# Power_Distribution_V2.net
KiCad netlist of a schematic drawn in EAGLE
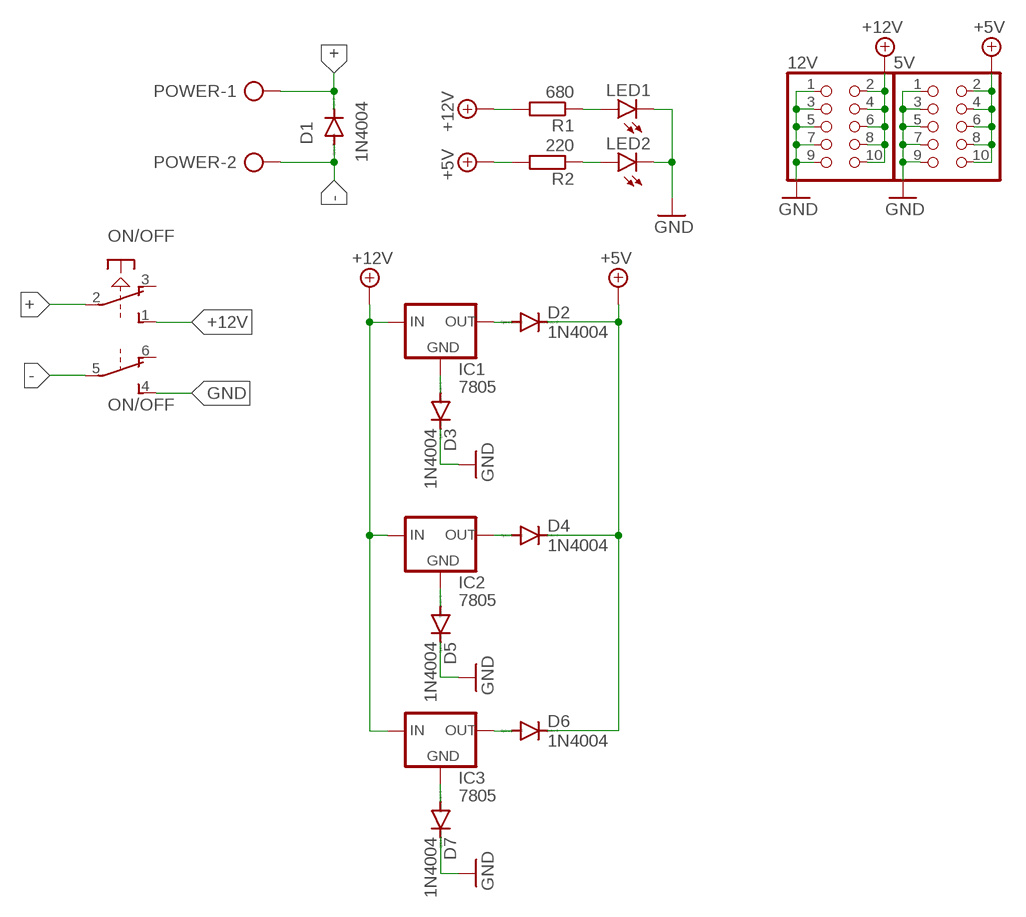
[diagram p0: schematic, sheet 1]

(export (version "E")
  (design (tool "Eeschema 10.0.6"))
  (components
    (comp (ref "5V")
      (value "PINHD-2X5")
      (footprint "eagle-import:2X05")
      (libsource (lib "eagle-import") (part "PINHD-2X5"))
    )
    (comp (ref "12V")
      (value "PINHD-2X5")
      (footprint "eagle-import:2X05")
      (libsource (lib "eagle-import") (part "PINHD-2X5"))
    )
    (comp (ref "D1")
      (value "1N4004")
      (footprint "eagle-import:DO41-10")
      (libsource (lib "eagle-import") (part "1N4004"))
    )
    (comp (ref "D2")
      (value "1N4004")
      (footprint "eagle-import:DO41-10")
      (libsource (lib "eagle-import") (part "1N4004"))
    )
    (comp (ref "D3")
      (value "1N4004")
      (footprint "eagle-import:DO41-10")
      (libsource (lib "eagle-import") (part "1N4004"))
    )
    (comp (ref "D4")
      (value "1N4004")
      (footprint "eagle-import:DO41-10")
      (libsource (lib "eagle-import") (part "1N4004"))
    )
    (comp (ref "D5")
      (value "1N4004")
      (footprint "eagle-import:DO41-10")
      (libsource (lib "eagle-import") (part "1N4004"))
    )
    (comp (ref "D6")
      (value "1N4004")
      (footprint "eagle-import:DO41-10")
      (libsource (lib "eagle-import") (part "1N4004"))
    )
    (comp (ref "D7")
      (value "1N4004")
      (footprint "eagle-import:DO41-10")
      (libsource (lib "eagle-import") (part "1N4004"))
    )
    (comp (ref "IC1")
      (value "7805")
      (footprint "eagle-import:78XXS")
      (libsource (lib "eagle-import") (part "78XXS"))
    )
    (comp (ref "IC2")
      (value "7805")
      (footprint "eagle-import:78XXS")
      (libsource (lib "eagle-import") (part "78XXS"))
    )
    (comp (ref "IC3")
      (value "7805")
      (footprint "eagle-import:78XXS")
      (libsource (lib "eagle-import") (part "78XXS"))
    )
    (comp (ref "LED1")
      (value "LED3MM")
      (footprint "eagle-import:LED3MM")
      (libsource (lib "eagle-import") (part "LED3MM"))
    )
    (comp (ref "LED2")
      (value "LED3MM")
      (footprint "eagle-import:LED3MM")
      (libsource (lib "eagle-import") (part "LED3MM"))
    )
    (comp (ref "ON/OFF")
      (value "PVA2R")
      (footprint "eagle-import:PVA2R")
      (libsource (lib "eagle-import") (part "PVA2R"))
    )
    (comp (ref "POWER")
      (value "AK500/2-H")
      (footprint "eagle-import:AK500_2-H")
      (libsource (lib "eagle-import") (part "AK500/2-H"))
    )
    (comp (ref "R1")
      (value "680")
      (footprint "eagle-import:0207_10")
      (libsource (lib "eagle-import") (part "R-EU_0207/10"))
    )
    (comp (ref "R2")
      (value "220")
      (footprint "eagle-import:0207_10")
      (libsource (lib "eagle-import") (part "R-EU_0207/10"))
    )
  )
  (nets
    (net (code "1") (name "+") (class "Default")
      (node (ref "D1") (pin "C") (pinfunction "C_C") (pintype "passive"))
      (node (ref "ON/OFF") (pin "2") (pinfunction "P_2") (pintype "passive"))
      (node (ref "POWER") (pin "1") (pinfunction "KL_1") (pintype "passive"))
    )
    (net (code "2") (name "+5V") (class "Default")
      (node (ref "5V") (pin "10") (pinfunction "10_10") (pintype "passive"))
      (node (ref "5V") (pin "2") (pinfunction "2_2") (pintype "passive"))
      (node (ref "5V") (pin "4") (pinfunction "4_4") (pintype "passive"))
      (node (ref "5V") (pin "6") (pinfunction "6_6") (pintype "passive"))
      (node (ref "5V") (pin "8") (pinfunction "8_8") (pintype "passive"))
      (node (ref "D2") (pin "C") (pinfunction "C_C") (pintype "passive"))
      (node (ref "D4") (pin "C") (pinfunction "C_C") (pintype "passive"))
      (node (ref "D6") (pin "C") (pinfunction "C_C") (pintype "passive"))
      (node (ref "R2") (pin "2") (pinfunction "2_2") (pintype "passive"))
    )
    (net (code "3") (name "+12V") (class "Default")
      (node (ref "12V") (pin "10") (pinfunction "10_10") (pintype "passive"))
      (node (ref "12V") (pin "2") (pinfunction "2_2") (pintype "passive"))
      (node (ref "12V") (pin "4") (pinfunction "4_4") (pintype "passive"))
      (node (ref "12V") (pin "6") (pinfunction "6_6") (pintype "passive"))
      (node (ref "12V") (pin "8") (pinfunction "8_8") (pintype "passive"))
      (node (ref "IC1") (pin "IN") (pinfunction "IN_IN") (pintype "input"))
      (node (ref "IC2") (pin "IN") (pinfunction "IN_IN") (pintype "input"))
      (node (ref "IC3") (pin "IN") (pinfunction "IN_IN") (pintype "input"))
      (node (ref "ON/OFF") (pin "1") (pinfunction "S_1") (pintype "passive"))
      (node (ref "R1") (pin "2") (pinfunction "2_2") (pintype "passive"))
    )
    (net (code "4") (name "-") (class "Default")
      (node (ref "D1") (pin "A") (pinfunction "A_A") (pintype "passive"))
      (node (ref "ON/OFF") (pin "5") (pinfunction "P_5") (pintype "passive"))
      (node (ref "POWER") (pin "2") (pinfunction "KL_2") (pintype "passive"))
    )
    (net (code "5") (name "GND") (class "Default")
      (node (ref "12V") (pin "1") (pinfunction "1_1") (pintype "passive"))
      (node (ref "12V") (pin "3") (pinfunction "3_3") (pintype "passive"))
      (node (ref "12V") (pin "5") (pinfunction "5_5") (pintype "passive"))
      (node (ref "12V") (pin "7") (pinfunction "7_7") (pintype "passive"))
      (node (ref "12V") (pin "9") (pinfunction "9_9") (pintype "passive"))
      (node (ref "5V") (pin "1") (pinfunction "1_1") (pintype "passive"))
      (node (ref "5V") (pin "3") (pinfunction "3_3") (pintype "passive"))
      (node (ref "5V") (pin "5") (pinfunction "5_5") (pintype "passive"))
      (node (ref "5V") (pin "7") (pinfunction "7_7") (pintype "passive"))
      (node (ref "5V") (pin "9") (pinfunction "9_9") (pintype "passive"))
      (node (ref "D3") (pin "C") (pinfunction "C_C") (pintype "passive"))
      (node (ref "D5") (pin "C") (pinfunction "C_C") (pintype "passive"))
      (node (ref "D7") (pin "C") (pinfunction "C_C") (pintype "passive"))
      (node (ref "LED1") (pin "K") (pinfunction "C_K") (pintype "passive"))
      (node (ref "LED2") (pin "K") (pinfunction "C_K") (pintype "passive"))
      (node (ref "ON/OFF") (pin "4") (pinfunction "S_4") (pintype "passive"))
    )
    (net (code "6") (name "Net-(D2-PadA)") (class "Default")
      (node (ref "D2") (pin "A") (pinfunction "A_A") (pintype "passive"))
      (node (ref "IC1") (pin "OUT") (pinfunction "OUT_OUT") (pintype "passive"))
    )
    (net (code "7") (name "Net-(D3-PadA)") (class "Default")
      (node (ref "D3") (pin "A") (pinfunction "A_A") (pintype "passive"))
      (node (ref "IC1") (pin "GND") (pinfunction "GND_GND") (pintype "input"))
    )
    (net (code "8") (name "Net-(D4-PadA)") (class "Default")
      (node (ref "D4") (pin "A") (pinfunction "A_A") (pintype "passive"))
      (node (ref "IC2") (pin "OUT") (pinfunction "OUT_OUT") (pintype "passive"))
    )
    (net (code "9") (name "Net-(D5-PadA)") (class "Default")
      (node (ref "D5") (pin "A") (pinfunction "A_A") (pintype "passive"))
      (node (ref "IC2") (pin "GND") (pinfunction "GND_GND") (pintype "input"))
    )
    (net (code "10") (name "Net-(D6-PadA)") (class "Default")
      (node (ref "D6") (pin "A") (pinfunction "A_A") (pintype "passive"))
      (node (ref "IC3") (pin "OUT") (pinfunction "OUT_OUT") (pintype "passive"))
    )
    (net (code "11") (name "Net-(D7-PadA)") (class "Default")
      (node (ref "D7") (pin "A") (pinfunction "A_A") (pintype "passive"))
      (node (ref "IC3") (pin "GND") (pinfunction "GND_GND") (pintype "input"))
    )
    (net (code "12") (name "Net-(LED1-PadA)") (class "Default")
      (node (ref "LED1") (pin "A") (pinfunction "A_A") (pintype "passive"))
      (node (ref "R1") (pin "1") (pinfunction "1_1") (pintype "passive"))
    )
    (net (code "13") (name "Net-(LED2-PadA)") (class "Default")
      (node (ref "LED2") (pin "A") (pinfunction "A_A") (pintype "passive"))
      (node (ref "R2") (pin "1") (pinfunction "1_1") (pintype "passive"))
    )
    (net (code "14") (name "unconnected-(ON/OFFA-O-Pad3)") (class "Default")
      (node (ref "ON/OFF") (pin "3") (pinfunction "O_3") (pintype "passive"))
    )
    (net (code "15") (name "unconnected-(ON/OFFB-O-Pad6)") (class "Default")
      (node (ref "ON/OFF") (pin "6") (pinfunction "O_6") (pintype "passive"))
    )
  )
)
